# nano-pwmsch.net
KiCad netlist of a schematic drawn in EAGLE
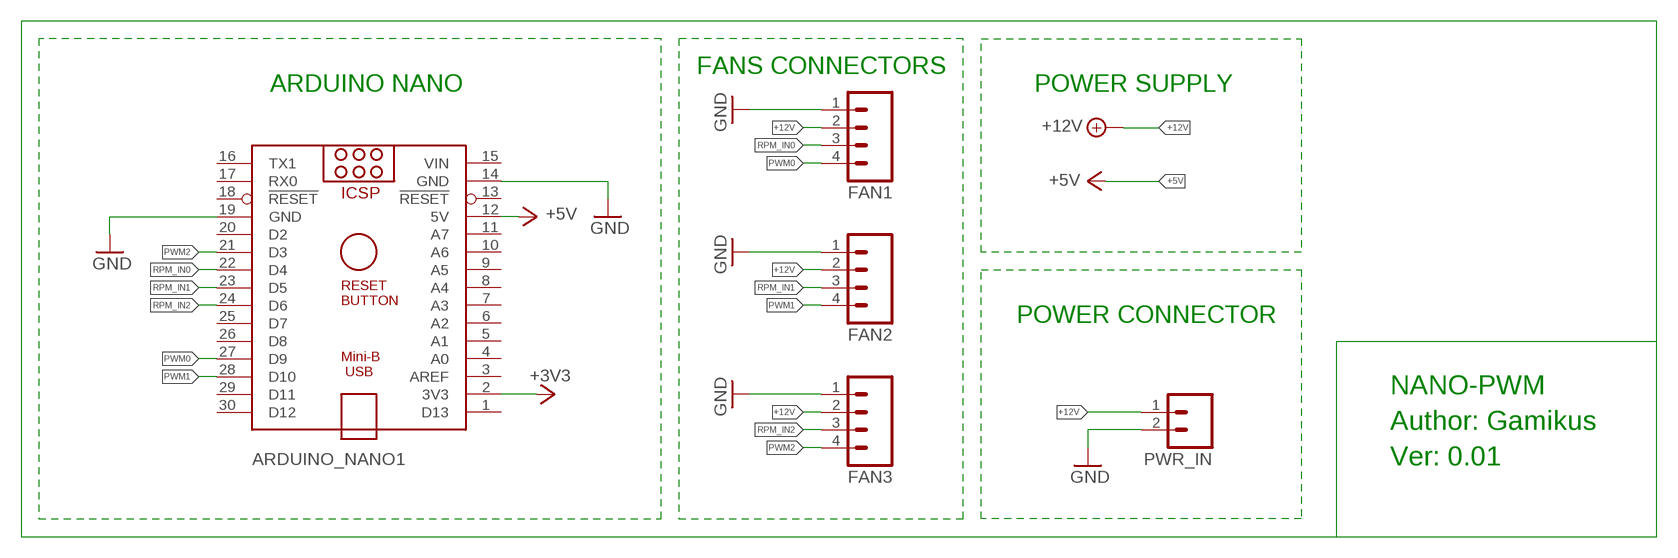
[diagram p0: schematic, sheet 1]

(export (version "E")
  (design (tool "Eeschema 10.0.6"))
  (components
    (comp (ref "ARDUINO_NANO1")
      (value "ARDUINO_NANO")
      (footprint "eagle-import:ARDUINO_NANO")
      (libsource (lib "eagle-import") (part "ARDUINO_NANO"))
    )
    (comp (ref "FAN1")
      (value "M04")
      (footprint "eagle-import:04P")
      (libsource (lib "eagle-import") (part "M04"))
    )
    (comp (ref "FAN2")
      (value "M04")
      (footprint "eagle-import:04P")
      (libsource (lib "eagle-import") (part "M04"))
    )
    (comp (ref "FAN3")
      (value "M04")
      (footprint "eagle-import:04P")
      (libsource (lib "eagle-import") (part "M04"))
    )
    (comp (ref "PWR_IN")
      (value "M02")
      (footprint "eagle-import:02P")
      (libsource (lib "eagle-import") (part "M02"))
    )
  )
  (nets
    (net (code "1") (name "+3V3") (class "Default")
      (node (ref "ARDUINO_NANO1") (pin "2") (pinfunction "3V3_2") (pintype "output"))
    )
    (net (code "2") (name "+5V") (class "Default")
      (node (ref "ARDUINO_NANO1") (pin "12") (pinfunction "5V_12") (pintype "power_in"))
    )
    (net (code "3") (name "+12V") (class "Default")
      (node (ref "FAN1") (pin "2") (pinfunction "2_2") (pintype "passive"))
      (node (ref "FAN2") (pin "2") (pinfunction "2_2") (pintype "passive"))
      (node (ref "FAN3") (pin "2") (pinfunction "2_2") (pintype "passive"))
      (node (ref "PWR_IN") (pin "1") (pinfunction "1_1") (pintype "passive"))
    )
    (net (code "4") (name "/VIN") (class "Default")
      (node (ref "ARDUINO_NANO1") (pin "15") (pinfunction "VIN_15") (pintype "power_in"))
    )
    (net (code "5") (name "GND") (class "Default")
      (node (ref "ARDUINO_NANO1") (pin "14") (pinfunction "GND_14") (pintype "power_in"))
      (node (ref "ARDUINO_NANO1") (pin "19") (pinfunction "GND_19") (pintype "power_in"))
      (node (ref "FAN1") (pin "1") (pinfunction "1_1") (pintype "passive"))
      (node (ref "FAN2") (pin "1") (pinfunction "1_1") (pintype "passive"))
      (node (ref "FAN3") (pin "1") (pinfunction "1_1") (pintype "passive"))
      (node (ref "PWR_IN") (pin "2") (pinfunction "2_2") (pintype "passive"))
    )
    (net (code "6") (name "PWM0") (class "Default")
      (node (ref "ARDUINO_NANO1") (pin "27") (pinfunction "D9_27") (pintype "bidirectional"))
      (node (ref "FAN1") (pin "4") (pinfunction "4_4") (pintype "passive"))
    )
    (net (code "7") (name "PWM1") (class "Default")
      (node (ref "ARDUINO_NANO1") (pin "28") (pinfunction "D10_28") (pintype "bidirectional"))
      (node (ref "FAN2") (pin "4") (pinfunction "4_4") (pintype "passive"))
    )
    (net (code "8") (name "PWM2") (class "Default")
      (node (ref "ARDUINO_NANO1") (pin "21") (pinfunction "D3_21") (pintype "bidirectional"))
      (node (ref "FAN3") (pin "4") (pinfunction "4_4") (pintype "passive"))
    )
    (net (code "9") (name "RPM_IN0") (class "Default")
      (node (ref "ARDUINO_NANO1") (pin "22") (pinfunction "D4_22") (pintype "bidirectional"))
      (node (ref "FAN1") (pin "3") (pinfunction "3_3") (pintype "passive"))
    )
    (net (code "10") (name "RPM_IN1") (class "Default")
      (node (ref "ARDUINO_NANO1") (pin "23") (pinfunction "D5_23") (pintype "bidirectional"))
      (node (ref "FAN2") (pin "3") (pinfunction "3_3") (pintype "passive"))
    )
    (net (code "11") (name "RPM_IN2") (class "Default")
      (node (ref "ARDUINO_NANO1") (pin "24") (pinfunction "D6_24") (pintype "bidirectional"))
      (node (ref "FAN3") (pin "3") (pinfunction "3_3") (pintype "passive"))
    )
    (net (code "12") (name "unconnected-(ARDUINO_NANO1-A0-Pad4)") (class "Default")
      (node (ref "ARDUINO_NANO1") (pin "4") (pinfunction "A0_4") (pintype "bidirectional"))
    )
    (net (code "13") (name "unconnected-(ARDUINO_NANO1-A1-Pad5)") (class "Default")
      (node (ref "ARDUINO_NANO1") (pin "5") (pinfunction "A1_5") (pintype "bidirectional"))
    )
    (net (code "14") (name "unconnected-(ARDUINO_NANO1-A2-Pad6)") (class "Default")
      (node (ref "ARDUINO_NANO1") (pin "6") (pinfunction "A2_6") (pintype "bidirectional"))
    )
    (net (code "15") (name "unconnected-(ARDUINO_NANO1-A3-Pad7)") (class "Default")
      (node (ref "ARDUINO_NANO1") (pin "7") (pinfunction "A3_7") (pintype "bidirectional"))
    )
    (net (code "16") (name "unconnected-(ARDUINO_NANO1-A4-Pad8)") (class "Default")
      (node (ref "ARDUINO_NANO1") (pin "8") (pinfunction "A4_8") (pintype "bidirectional"))
    )
    (net (code "17") (name "unconnected-(ARDUINO_NANO1-A5-Pad9)") (class "Default")
      (node (ref "ARDUINO_NANO1") (pin "9") (pinfunction "A5_9") (pintype "bidirectional"))
    )
    (net (code "18") (name "unconnected-(ARDUINO_NANO1-A6-Pad10)") (class "Default")
      (node (ref "ARDUINO_NANO1") (pin "10") (pinfunction "A6_10") (pintype "bidirectional"))
    )
    (net (code "19") (name "unconnected-(ARDUINO_NANO1-A7-Pad11)") (class "Default")
      (node (ref "ARDUINO_NANO1") (pin "11") (pinfunction "A7_11") (pintype "bidirectional"))
    )
    (net (code "20") (name "unconnected-(ARDUINO_NANO1-AREF-Pad3)") (class "Default")
      (node (ref "ARDUINO_NANO1") (pin "3") (pinfunction "AREF_3") (pintype "input"))
    )
    (net (code "21") (name "unconnected-(ARDUINO_NANO1-D2-Pad20)") (class "Default")
      (node (ref "ARDUINO_NANO1") (pin "20") (pinfunction "D2_20") (pintype "bidirectional"))
    )
    (net (code "22") (name "unconnected-(ARDUINO_NANO1-D7-Pad25)") (class "Default")
      (node (ref "ARDUINO_NANO1") (pin "25") (pinfunction "D7_25") (pintype "bidirectional"))
    )
    (net (code "23") (name "unconnected-(ARDUINO_NANO1-D8-Pad26)") (class "Default")
      (node (ref "ARDUINO_NANO1") (pin "26") (pinfunction "D8_26") (pintype "bidirectional"))
    )
    (net (code "24") (name "unconnected-(ARDUINO_NANO1-D11-Pad29)") (class "Default")
      (node (ref "ARDUINO_NANO1") (pin "29") (pinfunction "D11_29") (pintype "bidirectional"))
    )
    (net (code "25") (name "unconnected-(ARDUINO_NANO1-D12-Pad30)") (class "Default")
      (node (ref "ARDUINO_NANO1") (pin "30") (pinfunction "D12_30") (pintype "bidirectional"))
    )
    (net (code "26") (name "unconnected-(ARDUINO_NANO1-D13-Pad1)") (class "Default")
      (node (ref "ARDUINO_NANO1") (pin "1") (pinfunction "D13_1") (pintype "bidirectional"))
    )
    (net (code "27") (name "unconnected-(ARDUINO_NANO1-RX0-Pad17)") (class "Default")
      (node (ref "ARDUINO_NANO1") (pin "17") (pinfunction "RX0_17") (pintype "bidirectional"))
    )
    (net (code "28") (name "unconnected-(ARDUINO_NANO1-TX1-Pad16)") (class "Default")
      (node (ref "ARDUINO_NANO1") (pin "16") (pinfunction "TX1_16") (pintype "bidirectional"))
    )
    (net (code "29") (name "unconnected-(ARDUINO_NANO1-~{RESET}-Pad13)") (class "Default")
      (node (ref "ARDUINO_NANO1") (pin "13") (pinfunction "~{RESET}_13") (pintype "input"))
    )
    (net (code "30") (name "unconnected-(ARDUINO_NANO1-~{RESET}-Pad18)") (class "Default")
      (node (ref "ARDUINO_NANO1") (pin "18") (pinfunction "~{RESET}_18") (pintype "input"))
    )
  )
)
